# schem.net
KiCad netlist of a schematic drawn in Altium Designer
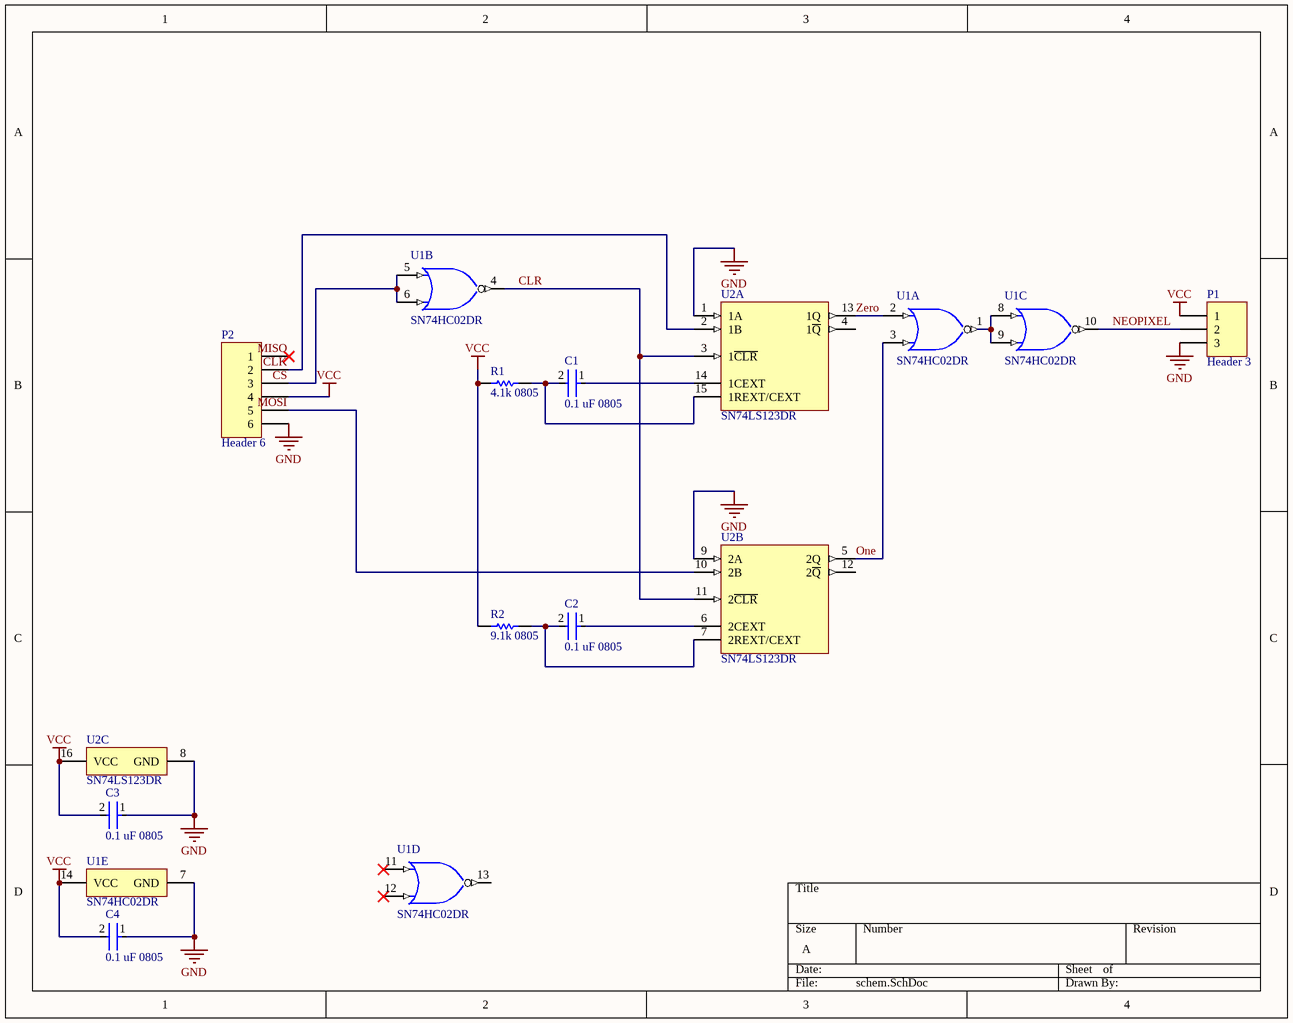
[diagram p0: schem.SchDoc]

(export (version "E")
  (design (tool "Eeschema 10.0.6"))
  (components
    (comp (ref "C1")
      (value "0.1 uF 0805")
      (footprint "FP-C0805C-DN-MFG")
      (description "CAP CER 0.1UF 100V X7R 0805")
      (fields (field (name "MANUFACTURER") "KEMET") (field (name "TOLERANCE") "0.1"))
      (libsource (lib "Altium Content Vault") (part "b4654b650e69147ec39a6b967a45e02"))
    )
    (comp (ref "C2")
      (value "0.1 uF 0805")
      (footprint "FP-C0805C-DN-MFG")
      (description "CAP CER 0.1UF 100V X7R 0805")
      (fields (field (name "MANUFACTURER") "KEMET") (field (name "TOLERANCE") "0.1"))
      (libsource (lib "Altium Content Vault") (part "b4654b650e69147ec39a6b967a45e02"))
    )
    (comp (ref "C3")
      (value "0.1 uF 0805")
      (footprint "FP-C0805C-DN-MFG")
      (description "CAP CER 0.1UF 100V X7R 0805")
      (fields (field (name "MANUFACTURER") "KEMET") (field (name "TOLERANCE") "0.1"))
      (libsource (lib "Altium Content Vault") (part "b4654b650e69147ec39a6b967a45e02"))
    )
    (comp (ref "C4")
      (value "0.1 uF 0805")
      (footprint "FP-C0805C-DN-MFG")
      (description "CAP CER 0.1UF 100V X7R 0805")
      (fields (field (name "MANUFACTURER") "KEMET") (field (name "TOLERANCE") "0.1"))
      (libsource (lib "Altium Content Vault") (part "b4654b650e69147ec39a6b967a45e02"))
    )
    (comp (ref "P1")
      (value "Header 3")
      (footprint "HDR1X3")
      (description "Header, 3-Pin")
      (fields (field (name "PUBLISHER") "Altium Limited"))
      (libsource (lib "Miscellaneous Connectors") (part "Header 3"))
    )
    (comp (ref "P2")
      (value "Header 6")
      (footprint "HDR1X6")
      (description "Header, 6-Pin")
      (fields (field (name "PUBLISHER") "Altium Limited"))
      (libsource (lib "Miscellaneous Connectors") (part "Header 6"))
    )
    (comp (ref "R1")
      (value "4.1k 0805")
      (footprint "RESC2013X50X30LL20T20")
      (fields (field (name "MANUFACTURER") "Vishay Dale") (field (name "PART NUMBER") "CRCW08050000Z0EA"))
      (libsource (lib "Altium Content Vault") (part "RES"))
    )
    (comp (ref "R2")
      (value "9.1k 0805")
      (footprint "RESC2013X50X30LL20T20")
      (fields (field (name "MANUFACTURER") "Vishay Dale") (field (name "PART NUMBER") "CRCW08050000Z0EA"))
      (libsource (lib "Altium Content Vault") (part "RES"))
    )
    (comp (ref "U1")
      (value "SN74HC02DR")
      (footprint "D0014A_L")
      (description "Quadruple 2-Input Positive-NOR Gates, D0014A, LARGE T&R")
      (fields
        (field (name "MANUFACTURER") "Texas Instruments")
        (field (name "GENERIC PART NUMBER") "SN74HC02")
      )
      (libsource (lib "Altium Content Vault") (part "TI-NOR-4-2IN-14"))
    )
    (comp (ref "U2")
      (value "SN74LS123DR")
      (footprint "D0016A_L")
      (description "Dual retriggerable monostable multivibrators, D0016A, LARGE T&R")
      (fields
        (field (name "GENERIC PART NUMBER") "SN74LS123")
        (field (name "MANUFACTURER") "Texas Instruments")
      )
      (libsource (lib "Altium Content Vault") (part "TI-SNX4XX123_221_423-16"))
    )
  )
  (nets
    (net (code "1") (name "/CLK") (class "Default")
      (node (ref "P2") (pin "2") (pinfunction "2_2") (pintype "passive"))
      (node (ref "U2") (pin "2") (pinfunction "1B_2") (pintype "input"))
    )
    (net (code "2") (name "/CLR") (class "Default")
      (node (ref "U1") (pin "4") (pinfunction "2Y_4") (pintype "output"))
      (node (ref "U2") (pin "11") (pinfunction "2~{CLR}_11") (pintype "input"))
      (node (ref "U2") (pin "3") (pinfunction "1~{CLR}_3") (pintype "input"))
    )
    (net (code "3") (name "/CS") (class "Default")
      (node (ref "P2") (pin "3") (pinfunction "3_3") (pintype "passive"))
      (node (ref "U1") (pin "5") (pinfunction "2A_5") (pintype "input"))
      (node (ref "U1") (pin "6") (pinfunction "2B_6") (pintype "input"))
    )
    (net (code "4") (name "/MISO") (class "Default")
      (node (ref "P2") (pin "1") (pinfunction "1_1") (pintype "passive+no_connect"))
    )
    (net (code "5") (name "/MOSI") (class "Default")
      (node (ref "P2") (pin "5") (pinfunction "5_5") (pintype "passive"))
      (node (ref "U2") (pin "10") (pinfunction "2B_10") (pintype "input"))
    )
    (net (code "6") (name "/NEOPIXEL") (class "Default")
      (node (ref "P1") (pin "2") (pinfunction "2_2") (pintype "passive"))
      (node (ref "U1") (pin "10") (pinfunction "3Y_10") (pintype "output"))
    )
    (net (code "7") (name "/One") (class "Default")
      (node (ref "U1") (pin "3") (pinfunction "1B_3") (pintype "input"))
      (node (ref "U2") (pin "5") (pinfunction "2Q_5") (pintype "output"))
    )
    (net (code "8") (name "/Zero") (class "Default")
      (node (ref "U1") (pin "2") (pinfunction "1A_2") (pintype "input"))
      (node (ref "U2") (pin "13") (pinfunction "1Q_13") (pintype "output"))
    )
    (net (code "9") (name "GND") (class "Default")
      (node (ref "C3") (pin "1") (pinfunction "1_1") (pintype "passive"))
      (node (ref "C4") (pin "1") (pinfunction "1_1") (pintype "passive"))
      (node (ref "P1") (pin "3") (pinfunction "3_3") (pintype "passive"))
      (node (ref "P2") (pin "6") (pinfunction "6_6") (pintype "passive"))
      (node (ref "U1") (pin "7") (pinfunction "GND_7") (pintype "power_in"))
      (node (ref "U2") (pin "1") (pinfunction "1A_1") (pintype "input"))
      (node (ref "U2") (pin "8") (pinfunction "GND_8") (pintype "power_in"))
      (node (ref "U2") (pin "9") (pinfunction "2A_9") (pintype "input"))
    )
    (net (code "10") (name "Net-(U1A-1Y)") (class "Default")
      (node (ref "U1") (pin "1") (pinfunction "1Y_1") (pintype "output"))
      (node (ref "U1") (pin "8") (pinfunction "3A_8") (pintype "input"))
      (node (ref "U1") (pin "9") (pinfunction "3B_9") (pintype "input"))
    )
    (net (code "11") (name "Net-(U2A-1CEXT)") (class "Default")
      (node (ref "C1") (pin "1") (pinfunction "1_1") (pintype "passive"))
      (node (ref "U2") (pin "14") (pinfunction "1CEXT_14") (pintype "passive"))
    )
    (net (code "12") (name "Net-(U2A-1REXT{slash}CEXT)") (class "Default")
      (node (ref "C1") (pin "2") (pinfunction "2_2") (pintype "passive"))
      (node (ref "R1") (pin "2") (pinfunction "2_2") (pintype "passive"))
      (node (ref "U2") (pin "15") (pinfunction "1REXT/CEXT_15") (pintype "passive"))
    )
    (net (code "13") (name "Net-(U2B-2CEXT)") (class "Default")
      (node (ref "C2") (pin "1") (pinfunction "1_1") (pintype "passive"))
      (node (ref "U2") (pin "6") (pinfunction "2CEXT_6") (pintype "passive"))
    )
    (net (code "14") (name "Net-(U2B-2REXT{slash}CEXT)") (class "Default")
      (node (ref "C2") (pin "2") (pinfunction "2_2") (pintype "passive"))
      (node (ref "R2") (pin "2") (pinfunction "2_2") (pintype "passive"))
      (node (ref "U2") (pin "7") (pinfunction "2REXT/CEXT_7") (pintype "passive"))
    )
    (net (code "15") (name "VCC") (class "Default")
      (node (ref "C3") (pin "2") (pinfunction "2_2") (pintype "passive"))
      (node (ref "C4") (pin "2") (pinfunction "2_2") (pintype "passive"))
      (node (ref "P1") (pin "1") (pinfunction "1_1") (pintype "passive"))
      (node (ref "P2") (pin "4") (pinfunction "4_4") (pintype "passive"))
      (node (ref "R1") (pin "1") (pinfunction "1_1") (pintype "passive"))
      (node (ref "R2") (pin "1") (pinfunction "1_1") (pintype "passive"))
      (node (ref "U1") (pin "14") (pinfunction "VCC_14") (pintype "power_in"))
      (node (ref "U2") (pin "16") (pinfunction "VCC_16") (pintype "power_in"))
    )
    (net (code "16") (name "unconnected-(U1D-4A-Pad11)") (class "Default")
      (node (ref "U1") (pin "11") (pinfunction "4A_11") (pintype "input+no_connect"))
    )
    (net (code "17") (name "unconnected-(U1D-4B-Pad12)") (class "Default")
      (node (ref "U1") (pin "12") (pinfunction "4B_12") (pintype "input+no_connect"))
    )
    (net (code "18") (name "unconnected-(U1D-4Y-Pad13)") (class "Default")
      (node (ref "U1") (pin "13") (pinfunction "4Y_13") (pintype "output"))
    )
    (net (code "19") (name "unconnected-(U2A-1~{Q}-Pad4)") (class "Default")
      (node (ref "U2") (pin "4") (pinfunction "1~{Q}_4") (pintype "output"))
    )
    (net (code "20") (name "unconnected-(U2B-2~{Q}-Pad12)") (class "Default")
      (node (ref "U2") (pin "12") (pinfunction "2~{Q}_12") (pintype "output"))
    )
  )
)
